# QRS959041_JiaLichuang.net
KiCad netlist of a schematic drawn in EasyEDA Pro
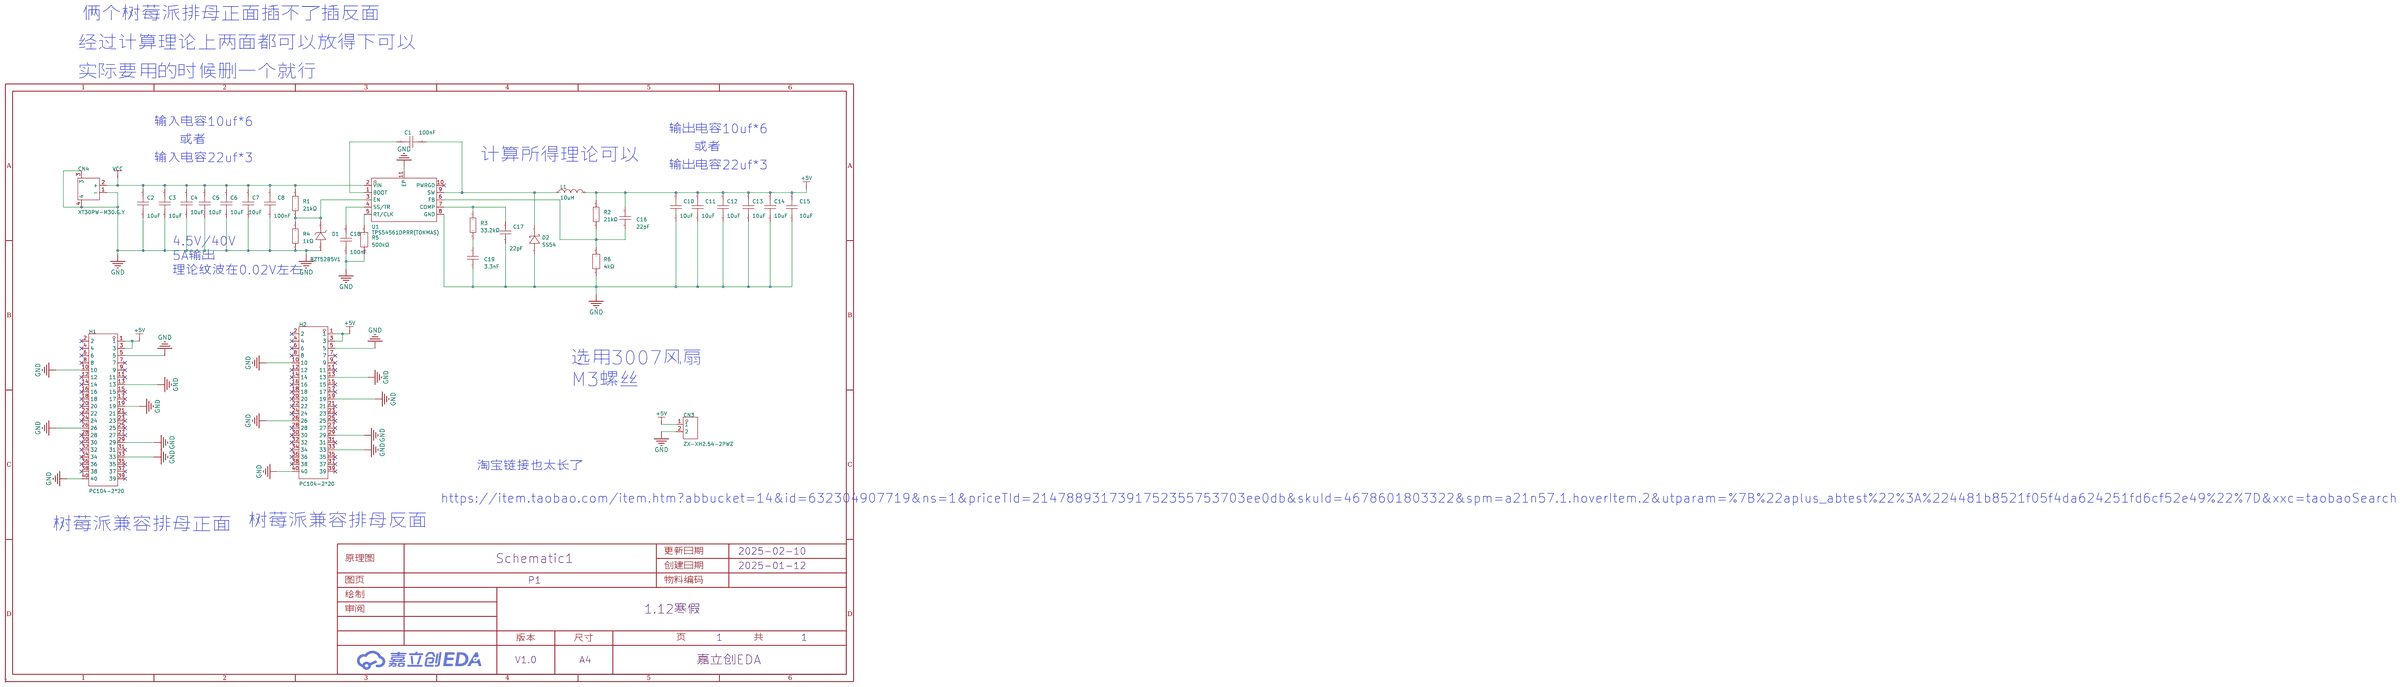
[diagram p0: schematic sheet]

(export (version "E")
  (design (tool "Eeschema 10.0.6"))
  (components
    (comp (ref "C1")
      (value "100nF")
      (footprint "easyedapro:C0603")
      (description "容值:100nF;精度:±10%;额定电压:50V;材质(温度系数):X7R;")
      (fields
        (field (name "Manufacturer Part") "CGA0603X7R104K500JT")
        (field (name "Manufacturer") "HRE(芯声)")
      )
      (libsource (lib "easyedapro") (part "CGA0603X7R104K500JT"))
    )
    (comp (ref "C2")
      (value "10uF")
      (footprint "easyedapro:C0805")
      (description "容值:10uF;精度:±10%;额定电压:50V;材质(温度系数):X5R;")
      (fields
        (field (name "Manufacturer Part") "GRM21BR61H106KE43L")
        (field (name "Manufacturer") "muRata(村田)")
      )
      (libsource (lib "easyedapro") (part "GRM21BR61H106KE43L"))
    )
    (comp (ref "C3")
      (value "10uF")
      (footprint "easyedapro:C0805")
      (description "容值:10uF;精度:±10%;额定电压:50V;材质(温度系数):X5R;")
      (fields
        (field (name "Manufacturer Part") "GRM21BR61H106KE43L")
        (field (name "Manufacturer") "muRata(村田)")
      )
      (libsource (lib "easyedapro") (part "GRM21BR61H106KE43L"))
    )
    (comp (ref "C4")
      (value "10uF")
      (footprint "easyedapro:C0805")
      (description "容值:10uF;精度:±10%;额定电压:50V;材质(温度系数):X5R;")
      (fields
        (field (name "Manufacturer Part") "GRM21BR61H106KE43L")
        (field (name "Manufacturer") "muRata(村田)")
      )
      (libsource (lib "easyedapro") (part "GRM21BR61H106KE43L"))
    )
    (comp (ref "C5")
      (value "10uF")
      (footprint "easyedapro:C0805")
      (description "容值:10uF;精度:±10%;额定电压:50V;材质(温度系数):X5R;")
      (fields
        (field (name "Manufacturer Part") "GRM21BR61H106KE43L")
        (field (name "Manufacturer") "muRata(村田)")
      )
      (libsource (lib "easyedapro") (part "GRM21BR61H106KE43L"))
    )
    (comp (ref "C6")
      (value "10uF")
      (footprint "easyedapro:C0805")
      (description "容值:10uF;精度:±10%;额定电压:50V;材质(温度系数):X5R;")
      (fields
        (field (name "Manufacturer Part") "GRM21BR61H106KE43L")
        (field (name "Manufacturer") "muRata(村田)")
      )
      (libsource (lib "easyedapro") (part "GRM21BR61H106KE43L"))
    )
    (comp (ref "C7")
      (value "10uF")
      (footprint "easyedapro:C0805")
      (description "容值:10uF;精度:±10%;额定电压:50V;材质(温度系数):X5R;")
      (fields
        (field (name "Manufacturer Part") "GRM21BR61H106KE43L")
        (field (name "Manufacturer") "muRata(村田)")
      )
      (libsource (lib "easyedapro") (part "GRM21BR61H106KE43L"))
    )
    (comp (ref "C8")
      (value "100nF")
      (footprint "easyedapro:C0603")
      (description "容值:100nF;精度:±10%;额定电压:50V;材质(温度系数):X7R;")
      (fields
        (field (name "Manufacturer Part") "CGA0603X7R104K500JT")
        (field (name "Manufacturer") "HRE(芯声)")
      )
      (libsource (lib "easyedapro") (part "CGA0603X7R104K500JT"))
    )
    (comp (ref "C10")
      (value "10uF")
      (footprint "easyedapro:C0805")
      (description "容值:10uF;精度:±10%;额定电压:50V;材质(温度系数):X5R;")
      (fields
        (field (name "Manufacturer Part") "GRM21BR61H106KE43L")
        (field (name "Manufacturer") "muRata(村田)")
      )
      (libsource (lib "easyedapro") (part "GRM21BR61H106KE43L"))
    )
    (comp (ref "C11")
      (value "10uF")
      (footprint "easyedapro:C0805")
      (description "容值:10uF;精度:±10%;额定电压:50V;材质(温度系数):X5R;")
      (fields
        (field (name "Manufacturer Part") "GRM21BR61H106KE43L")
        (field (name "Manufacturer") "muRata(村田)")
      )
      (libsource (lib "easyedapro") (part "GRM21BR61H106KE43L"))
    )
    (comp (ref "C12")
      (value "10uF")
      (footprint "easyedapro:C0805")
      (description "容值:10uF;精度:±10%;额定电压:50V;材质(温度系数):X5R;")
      (fields
        (field (name "Manufacturer Part") "GRM21BR61H106KE43L")
        (field (name "Manufacturer") "muRata(村田)")
      )
      (libsource (lib "easyedapro") (part "GRM21BR61H106KE43L"))
    )
    (comp (ref "C13")
      (value "10uF")
      (footprint "easyedapro:C0805")
      (description "容值:10uF;精度:±10%;额定电压:50V;材质(温度系数):X5R;")
      (fields
        (field (name "Manufacturer Part") "GRM21BR61H106KE43L")
        (field (name "Manufacturer") "muRata(村田)")
      )
      (libsource (lib "easyedapro") (part "GRM21BR61H106KE43L"))
    )
    (comp (ref "C14")
      (value "10uF")
      (footprint "easyedapro:C0805")
      (description "容值:10uF;精度:±10%;额定电压:50V;材质(温度系数):X5R;")
      (fields
        (field (name "Manufacturer Part") "GRM21BR61H106KE43L")
        (field (name "Manufacturer") "muRata(村田)")
      )
      (libsource (lib "easyedapro") (part "GRM21BR61H106KE43L"))
    )
    (comp (ref "C15")
      (value "10uF")
      (footprint "easyedapro:C0805")
      (description "容值:10uF;精度:±10%;额定电压:50V;材质(温度系数):X5R;")
      (fields
        (field (name "Manufacturer Part") "GRM21BR61H106KE43L")
        (field (name "Manufacturer") "muRata(村田)")
      )
      (libsource (lib "easyedapro") (part "GRM21BR61H106KE43L"))
    )
    (comp (ref "C16")
      (value "22pF")
      (footprint "easyedapro:C0603")
      (description "容值:22pF;精度:±5%;额定电压:50V;材质(温度系数):NP0;")
      (fields
        (field (name "Manufacturer Part") "CC0603JRNPO9BN220")
        (field (name "Manufacturer") "YAGEO(国巨)")
      )
      (libsource (lib "easyedapro") (part "CC0603JRNPO9BN220"))
    )
    (comp (ref "C17")
      (value "22pF")
      (footprint "easyedapro:C0603")
      (description "容值:22pF;精度:±5%;额定电压:50V;材质(温度系数):NP0;")
      (fields
        (field (name "Manufacturer Part") "CC0603JRNPO9BN220")
        (field (name "Manufacturer") "YAGEO(国巨)")
      )
      (libsource (lib "easyedapro") (part "CC0603JRNPO9BN220"))
    )
    (comp (ref "C18")
      (value "100nF")
      (footprint "easyedapro:C0603")
      (description "容值:100nF;精度:±10%;额定电压:50V;材质(温度系数):X7R;")
      (fields
        (field (name "Manufacturer Part") "CGA0603X7R104K500JT")
        (field (name "Manufacturer") "HRE(芯声)")
      )
      (libsource (lib "easyedapro") (part "CGA0603X7R104K500JT"))
    )
    (comp (ref "C19")
      (value "3.3nF")
      (footprint "easyedapro:C0603")
      (description "容值:3.3nF;精度:±10%;额定电压:50V;材质(温度系数):X7R;")
      (fields
        (field (name "Manufacturer Part") "CL10B332KB8NNNC")
        (field (name "Manufacturer") "SAMSUNG(三星)")
      )
      (libsource (lib "easyedapro") (part "CL10B332KB8NNNC"))
    )
    (comp (ref "CN3")
      (value "ZX-XH2.54-2PWZ")
      (footprint "easyedapro:CONN-TH_2P-P2.50_ZX-XH2.54-2PWZ")
      (fields (field (name "Manufacturer") "Megastar(兆星)"))
      (libsource (lib "easyedapro") (part "ZX-XH2.54-2PWZ"))
    )
    (comp (ref "CN4")
      (value "XT30PW-M30.G.Y")
      (footprint "easyedapro:CONN-TH_XT30PW-M")
      (description "类别:-;类型1:-;")
      (fields (field (name "Manufacturer") "AMASS(艾迈斯)"))
      (libsource (lib "easyedapro") (part "XT30PW-M"))
    )
    (comp (ref "D1")
      (value "BZT52B5V1")
      (footprint "easyedapro:SOD-123_L2.7-W1.6-LS3.7-RD")
      (description "二极管配置:独立式;稳压值(标称值):5.1V;稳压值(范围):5V~5.2V;功率(Pd):500mW;")
      (fields (field (name "Manufacturer") "宏迦橙"))
      (libsource (lib "easyedapro") (part "BZT52B5V1_C19077393"))
    )
    (comp (ref "D2")
      (value "SS54")
      (footprint "easyedapro:SMA_L4.3-W2.6-LS5.0-FD")
      (description "二极管配置:独立式;正向压降(Vf):550mV@5.0A;直流反向耐压(Vr):40V;整流电流:5A;")
      (fields (field (name "Manufacturer") "宏迦橙"))
      (libsource (lib "easyedapro") (part "SS54_C7420369"))
    )
    (comp (ref "H1")
      (value "PC104-2*20")
      (footprint "easyedapro:HDR-TH_40P-P2.54-V-F-R2-C20-S2.54-2")
      (fields (field (name "Manufacturer") "ZHOURI(洲日)"))
      (libsource (lib "easyedapro") (part "PC104-2*20"))
    )
    (comp (ref "H2")
      (value "PC104-2*20")
      (footprint "easyedapro:HDR-TH_40P-P2.54-V-F-R2-C20-S2.54-2")
      (fields (field (name "Manufacturer") "ZHOURI(洲日)"))
      (libsource (lib "easyedapro") (part "PC104-2*20"))
    )
    (comp (ref "L1")
      (value "10uH")
      (footprint "easyedapro:IND-SMD_L7.3-W6.8")
      (description "电感值:10uH;精度:±20%;额定电流:4.5A;饱和电流(Isat):5.5A;类型:一体成型电感;")
      (fields (field (name "Manufacturer Part") "FXL0630-100-M") (field (name "Manufacturer") "cjiang(长江微电)"))
      (libsource (lib "easyedapro") (part "FXL0630-100-M"))
    )
    (comp (ref "R1")
      (value "21kΩ")
      (footprint "easyedapro:R0603")
      (description "电阻类型:厚膜电阻;阻值:21kΩ;精度:±1%;功率:100mW;最大工作电压:75V;温度系数:±100ppm/°C;")
      (fields
        (field (name "Manufacturer Part") "0603WAF2102T5E")
        (field (name "Manufacturer") "UNI-ROYAL(厚声)")
      )
      (libsource (lib "easyedapro") (part "0603WAF2102T5E"))
    )
    (comp (ref "R2")
      (value "21kΩ")
      (footprint "easyedapro:R0603")
      (description "电阻类型:厚膜电阻;阻值:21kΩ;精度:±1%;功率:100mW;最大工作电压:75V;温度系数:±100ppm/°C;")
      (fields
        (field (name "Manufacturer Part") "0603WAF2102T5E")
        (field (name "Manufacturer") "UNI-ROYAL(厚声)")
      )
      (libsource (lib "easyedapro") (part "0603WAF2102T5E"))
    )
    (comp (ref "R3")
      (value "33.2kΩ")
      (footprint "easyedapro:R0603")
      (description "电阻类型:厚膜电阻;阻值:33.2kΩ;精度:±1%;功率:100mW;最大工作电压:75V;温度系数:±100ppm/°C;")
      (fields (field (name "Manufacturer Part") "RC0603FR-0733K2L") (field (name "Manufacturer") "YAGEO(国巨)"))
      (libsource (lib "easyedapro") (part "RC0603FR-0733K2L"))
    )
    (comp (ref "R4")
      (value "1kΩ")
      (footprint "easyedapro:R0603")
      (description "电阻类型:厚膜电阻;阻值:1kΩ;精度:±1%;功率:100mW;最大工作电压:75V;温度系数:±100ppm/°C;")
      (fields
        (field (name "Manufacturer Part") "0603WAF1001T5E")
        (field (name "Manufacturer") "UNI-ROYAL(厚声)")
      )
      (libsource (lib "easyedapro") (part "0603WAF1001T5E"))
    )
    (comp (ref "R5")
      (value "500kΩ")
      (footprint "easyedapro:R0603")
      (description "电阻类型:薄膜电阻;阻值:500kΩ;精度:±0.1%;功率:100mW;最大工作电压:50V;温度系数:±25ppm/°C;")
      (fields (field (name "Manufacturer Part") "AR03BTCX5003N") (field (name "Manufacturer") "Viking(光颉)"))
      (libsource (lib "easyedapro") (part "AR03BTCX5003N"))
    )
    (comp (ref "R6")
      (value "4kΩ")
      (footprint "easyedapro:R0603")
      (description "电阻类型:薄膜电阻;阻值:4kΩ;精度:±1%;")
      (fields (field (name "Manufacturer Part") "ARG03FTC4001N") (field (name "Manufacturer") "Viking(光颉)"))
      (libsource (lib "easyedapro") (part "ARG03FTC4001N"))
    )
    (comp (ref "U1")
      (value "TPS54561DPRR(TOKMAS)")
      (footprint "easyedapro:WDFN-10_L4.0-W4.0-P0.80-BL-EP")
      (description "功能类型:降压型;输出类型:可调;输入电压:4.5V~60V;输出电压:800mV~59V;输出电流(最大值):5A;")
      (fields (field (name "Manufacturer") "Tokmas(托克马斯)"))
      (libsource (lib "easyedapro") (part "TPS54561DPRR(TOKMAS)"))
    )
  )
  (nets
    (net (code "1") (name "+5V") (class "Default")
      (node (ref "C10") (pin "2") (pinfunction "2_2") (pintype "unspecified"))
      (node (ref "C11") (pin "2") (pinfunction "2_2") (pintype "unspecified"))
      (node (ref "C12") (pin "2") (pinfunction "2_2") (pintype "unspecified"))
      (node (ref "C13") (pin "2") (pinfunction "2_2") (pintype "unspecified"))
      (node (ref "C14") (pin "2") (pinfunction "2_2") (pintype "unspecified"))
      (node (ref "C15") (pin "2") (pinfunction "2_2") (pintype "unspecified"))
      (node (ref "C16") (pin "1") (pinfunction "1_1") (pintype "input"))
      (node (ref "CN3") (pin "1") (pinfunction "1_1") (pintype "unspecified"))
      (node (ref "H1") (pin "1") (pinfunction "1_1") (pintype "unspecified"))
      (node (ref "H1") (pin "3") (pinfunction "3_3") (pintype "unspecified"))
      (node (ref "H2") (pin "1") (pinfunction "1_1") (pintype "unspecified"))
      (node (ref "H2") (pin "3") (pinfunction "3_3") (pintype "unspecified"))
      (node (ref "L1") (pin "2") (pinfunction "2_2") (pintype "unspecified"))
      (node (ref "R2") (pin "2") (pinfunction "2_2") (pintype "input"))
    )
    (net (code "2") (name "GND") (class "Default")
      (node (ref "C10") (pin "1") (pinfunction "1_1") (pintype "unspecified"))
      (node (ref "C11") (pin "1") (pinfunction "1_1") (pintype "unspecified"))
      (node (ref "C12") (pin "1") (pinfunction "1_1") (pintype "unspecified"))
      (node (ref "C13") (pin "1") (pinfunction "1_1") (pintype "unspecified"))
      (node (ref "C14") (pin "1") (pinfunction "1_1") (pintype "unspecified"))
      (node (ref "C15") (pin "1") (pinfunction "1_1") (pintype "unspecified"))
      (node (ref "C17") (pin "2") (pinfunction "2_2") (pintype "input"))
      (node (ref "C18") (pin "1") (pinfunction "1_1") (pintype "unspecified"))
      (node (ref "C19") (pin "1") (pinfunction "1_1") (pintype "input"))
      (node (ref "C2") (pin "1") (pinfunction "1_1") (pintype "unspecified"))
      (node (ref "C3") (pin "1") (pinfunction "1_1") (pintype "unspecified"))
      (node (ref "C4") (pin "1") (pinfunction "1_1") (pintype "unspecified"))
      (node (ref "C5") (pin "1") (pinfunction "1_1") (pintype "unspecified"))
      (node (ref "C6") (pin "1") (pinfunction "1_1") (pintype "unspecified"))
      (node (ref "C7") (pin "1") (pinfunction "1_1") (pintype "unspecified"))
      (node (ref "C8") (pin "1") (pinfunction "1_1") (pintype "unspecified"))
      (node (ref "CN3") (pin "2") (pinfunction "2_2") (pintype "unspecified"))
      (node (ref "CN4") (pin "1") (pinfunction "-_1") (pintype "unspecified"))
      (node (ref "CN4") (pin "3") (pinfunction "3_3") (pintype "unspecified"))
      (node (ref "CN4") (pin "4") (pinfunction "4_4") (pintype "unspecified"))
      (node (ref "D1") (pin "2") (pinfunction "A_2") (pintype "unspecified"))
      (node (ref "D2") (pin "1") (pinfunction "A_1") (pintype "unspecified"))
      (node (ref "H1") (pin "10") (pinfunction "10_10") (pintype "unspecified"))
      (node (ref "H1") (pin "13") (pinfunction "13_13") (pintype "unspecified"))
      (node (ref "H1") (pin "19") (pinfunction "19_19") (pintype "unspecified"))
      (node (ref "H1") (pin "26") (pinfunction "26_26") (pintype "unspecified"))
      (node (ref "H1") (pin "29") (pinfunction "29_29") (pintype "unspecified"))
      (node (ref "H1") (pin "33") (pinfunction "33_33") (pintype "unspecified"))
      (node (ref "H1") (pin "40") (pinfunction "40_40") (pintype "unspecified"))
      (node (ref "H1") (pin "5") (pinfunction "5_5") (pintype "unspecified"))
      (node (ref "H2") (pin "10") (pinfunction "10_10") (pintype "unspecified"))
      (node (ref "H2") (pin "13") (pinfunction "13_13") (pintype "unspecified"))
      (node (ref "H2") (pin "19") (pinfunction "19_19") (pintype "unspecified"))
      (node (ref "H2") (pin "26") (pinfunction "26_26") (pintype "unspecified"))
      (node (ref "H2") (pin "29") (pinfunction "29_29") (pintype "unspecified"))
      (node (ref "H2") (pin "33") (pinfunction "33_33") (pintype "unspecified"))
      (node (ref "H2") (pin "40") (pinfunction "40_40") (pintype "unspecified"))
      (node (ref "H2") (pin "5") (pinfunction "5_5") (pintype "unspecified"))
      (node (ref "R4") (pin "1") (pinfunction "1_1") (pintype "input"))
      (node (ref "R5") (pin "1") (pinfunction "1_1") (pintype "unspecified"))
      (node (ref "R6") (pin "1") (pinfunction "1_1") (pintype "unspecified"))
      (node (ref "U1") (pin "11") (pinfunction "EP_11") (pintype "unspecified"))
      (node (ref "U1") (pin "8") (pinfunction "GND_8") (pintype "unspecified"))
    )
    (net (code "3") (name "Net-(C19-Pad2)") (class "Default")
      (node (ref "C19") (pin "2") (pinfunction "2_2") (pintype "input"))
      (node (ref "R3") (pin "1") (pinfunction "1_1") (pintype "unspecified"))
    )
    (net (code "4") (name "Net-(D1-K)") (class "Default")
      (node (ref "D1") (pin "1") (pinfunction "K_1") (pintype "unspecified"))
      (node (ref "R1") (pin "1") (pinfunction "1_1") (pintype "input"))
      (node (ref "R4") (pin "2") (pinfunction "2_2") (pintype "input"))
      (node (ref "U1") (pin "3") (pinfunction "EN_3") (pintype "unspecified"))
    )
    (net (code "5") (name "Net-(D2-K)") (class "Default")
      (node (ref "C1") (pin "2") (pinfunction "2_2") (pintype "unspecified"))
      (node (ref "D2") (pin "2") (pinfunction "K_2") (pintype "unspecified"))
      (node (ref "L1") (pin "1") (pinfunction "1_1") (pintype "unspecified"))
      (node (ref "U1") (pin "9") (pinfunction "SW_9") (pintype "unspecified"))
    )
    (net (code "6") (name "Net-(U1-BOOT)") (class "Default")
      (node (ref "C1") (pin "1") (pinfunction "1_1") (pintype "unspecified"))
      (node (ref "U1") (pin "1") (pinfunction "BOOT_1") (pintype "unspecified"))
    )
    (net (code "7") (name "Net-(U1-COMP)") (class "Default")
      (node (ref "C17") (pin "1") (pinfunction "1_1") (pintype "input"))
      (node (ref "R3") (pin "2") (pinfunction "2_2") (pintype "unspecified"))
      (node (ref "U1") (pin "7") (pinfunction "COMP_7") (pintype "unspecified"))
    )
    (net (code "8") (name "Net-(U1-FB)") (class "Default")
      (node (ref "C16") (pin "2") (pinfunction "2_2") (pintype "input"))
      (node (ref "R2") (pin "1") (pinfunction "1_1") (pintype "input"))
      (node (ref "R6") (pin "2") (pinfunction "2_2") (pintype "unspecified"))
      (node (ref "U1") (pin "6") (pinfunction "FB_6") (pintype "unspecified"))
    )
    (net (code "9") (name "Net-(U1-RT{slash}CLK)") (class "Default")
      (node (ref "R5") (pin "2") (pinfunction "2_2") (pintype "unspecified"))
      (node (ref "U1") (pin "5") (pinfunction "RT/CLK_5") (pintype "unspecified"))
    )
    (net (code "10") (name "Net-(U1-SS{slash}TR)") (class "Default")
      (node (ref "C18") (pin "2") (pinfunction "2_2") (pintype "unspecified"))
      (node (ref "U1") (pin "4") (pinfunction "SS/TR_4") (pintype "unspecified"))
    )
    (net (code "11") (name "VCC") (class "Default")
      (node (ref "C2") (pin "2") (pinfunction "2_2") (pintype "unspecified"))
      (node (ref "C3") (pin "2") (pinfunction "2_2") (pintype "unspecified"))
      (node (ref "C4") (pin "2") (pinfunction "2_2") (pintype "unspecified"))
      (node (ref "C5") (pin "2") (pinfunction "2_2") (pintype "unspecified"))
      (node (ref "C6") (pin "2") (pinfunction "2_2") (pintype "unspecified"))
      (node (ref "C7") (pin "2") (pinfunction "2_2") (pintype "unspecified"))
      (node (ref "C8") (pin "2") (pinfunction "2_2") (pintype "unspecified"))
      (node (ref "CN4") (pin "2") (pinfunction "+_2") (pintype "unspecified"))
      (node (ref "R1") (pin "2") (pinfunction "2_2") (pintype "input"))
      (node (ref "U1") (pin "2") (pinfunction "VIN_2") (pintype "unspecified"))
    )
    (net (code "12") (name "unconnected-(H1-Pad2)") (class "Default")
      (node (ref "H1") (pin "2") (pinfunction "2_2") (pintype "unspecified+no_connect"))
    )
    (net (code "13") (name "unconnected-(H1-Pad4)") (class "Default")
      (node (ref "H1") (pin "4") (pinfunction "4_4") (pintype "unspecified+no_connect"))
    )
    (net (code "14") (name "unconnected-(H1-Pad6)") (class "Default")
      (node (ref "H1") (pin "6") (pinfunction "6_6") (pintype "unspecified+no_connect"))
    )
    (net (code "15") (name "unconnected-(H1-Pad7)") (class "Default")
      (node (ref "H1") (pin "7") (pinfunction "7_7") (pintype "unspecified+no_connect"))
    )
    (net (code "16") (name "unconnected-(H1-Pad8)") (class "Default")
      (node (ref "H1") (pin "8") (pinfunction "8_8") (pintype "unspecified+no_connect"))
    )
    (net (code "17") (name "unconnected-(H1-Pad9)") (class "Default")
      (node (ref "H1") (pin "9") (pinfunction "9_9") (pintype "unspecified+no_connect"))
    )
    (net (code "18") (name "unconnected-(H1-Pad11)") (class "Default")
      (node (ref "H1") (pin "11") (pinfunction "11_11") (pintype "unspecified+no_connect"))
    )
    (net (code "19") (name "unconnected-(H1-Pad12)") (class "Default")
      (node (ref "H1") (pin "12") (pinfunction "12_12") (pintype "unspecified+no_connect"))
    )
    (net (code "20") (name "unconnected-(H1-Pad14)") (class "Default")
      (node (ref "H1") (pin "14") (pinfunction "14_14") (pintype "unspecified+no_connect"))
    )
    (net (code "21") (name "unconnected-(H1-Pad15)") (class "Default")
      (node (ref "H1") (pin "15") (pinfunction "15_15") (pintype "unspecified+no_connect"))
    )
    (net (code "22") (name "unconnected-(H1-Pad16)") (class "Default")
      (node (ref "H1") (pin "16") (pinfunction "16_16") (pintype "unspecified+no_connect"))
    )
    (net (code "23") (name "unconnected-(H1-Pad17)") (class "Default")
      (node (ref "H1") (pin "17") (pinfunction "17_17") (pintype "unspecified+no_connect"))
    )
    (net (code "24") (name "unconnected-(H1-Pad18)") (class "Default")
      (node (ref "H1") (pin "18") (pinfunction "18_18") (pintype "unspecified+no_connect"))
    )
    (net (code "25") (name "unconnected-(H1-Pad20)") (class "Default")
      (node (ref "H1") (pin "20") (pinfunction "20_20") (pintype "unspecified+no_connect"))
    )
    (net (code "26") (name "unconnected-(H1-Pad21)") (class "Default")
      (node (ref "H1") (pin "21") (pinfunction "21_21") (pintype "unspecified+no_connect"))
    )
    (net (code "27") (name "unconnected-(H1-Pad22)") (class "Default")
      (node (ref "H1") (pin "22") (pinfunction "22_22") (pintype "unspecified+no_connect"))
    )
    (net (code "28") (name "unconnected-(H1-Pad23)") (class "Default")
      (node (ref "H1") (pin "23") (pinfunction "23_23") (pintype "unspecified+no_connect"))
    )
    (net (code "29") (name "unconnected-(H1-Pad24)") (class "Default")
      (node (ref "H1") (pin "24") (pinfunction "24_24") (pintype "unspecified+no_connect"))
    )
    (net (code "30") (name "unconnected-(H1-Pad25)") (class "Default")
      (node (ref "H1") (pin "25") (pinfunction "25_25") (pintype "unspecified+no_connect"))
    )
    (net (code "31") (name "unconnected-(H1-Pad27)") (class "Default")
      (node (ref "H1") (pin "27") (pinfunction "27_27") (pintype "unspecified+no_connect"))
    )
    (net (code "32") (name "unconnected-(H1-Pad28)") (class "Default")
      (node (ref "H1") (pin "28") (pinfunction "28_28") (pintype "unspecified+no_connect"))
    )
    (net (code "33") (name "unconnected-(H1-Pad30)") (class "Default")
      (node (ref "H1") (pin "30") (pinfunction "30_30") (pintype "unspecified+no_connect"))
    )
    (net (code "34") (name "unconnected-(H1-Pad31)") (class "Default")
      (node (ref "H1") (pin "31") (pinfunction "31_31") (pintype "unspecified+no_connect"))
    )
    (net (code "35") (name "unconnected-(H1-Pad32)") (class "Default")
      (node (ref "H1") (pin "32") (pinfunction "32_32") (pintype "unspecified+no_connect"))
    )
    (net (code "36") (name "unconnected-(H1-Pad34)") (class "Default")
      (node (ref "H1") (pin "34") (pinfunction "34_34") (pintype "unspecified+no_connect"))
    )
    (net (code "37") (name "unconnected-(H1-Pad35)") (class "Default")
      (node (ref "H1") (pin "35") (pinfunction "35_35") (pintype "unspecified+no_connect"))
    )
    (net (code "38") (name "unconnected-(H1-Pad36)") (class "Default")
      (node (ref "H1") (pin "36") (pinfunction "36_36") (pintype "unspecified+no_connect"))
    )
    (net (code "39") (name "unconnected-(H1-Pad37)") (class "Default")
      (node (ref "H1") (pin "37") (pinfunction "37_37") (pintype "unspecified+no_connect"))
    )
    (net (code "40") (name "unconnected-(H1-Pad38)") (class "Default")
      (node (ref "H1") (pin "38") (pinfunction "38_38") (pintype "unspecified+no_connect"))
    )
    (net (code "41") (name "unconnected-(H1-Pad39)") (class "Default")
      (node (ref "H1") (pin "39") (pinfunction "39_39") (pintype "unspecified+no_connect"))
    )
    (net (code "42") (name "unconnected-(H2-Pad2)") (class "Default")
      (node (ref "H2") (pin "2") (pinfunction "2_2") (pintype "unspecified+no_connect"))
    )
    (net (code "43") (name "unconnected-(H2-Pad4)") (class "Default")
      (node (ref "H2") (pin "4") (pinfunction "4_4") (pintype "unspecified+no_connect"))
    )
    (net (code "44") (name "unconnected-(H2-Pad6)") (class "Default")
      (node (ref "H2") (pin "6") (pinfunction "6_6") (pintype "unspecified+no_connect"))
    )
    (net (code "45") (name "unconnected-(H2-Pad7)") (class "Default")
      (node (ref "H2") (pin "7") (pinfunction "7_7") (pintype "unspecified+no_connect"))
    )
    (net (code "46") (name "unconnected-(H2-Pad8)") (class "Default")
      (node (ref "H2") (pin "8") (pinfunction "8_8") (pintype "unspecified+no_connect"))
    )
    (net (code "47") (name "unconnected-(H2-Pad9)") (class "Default")
      (node (ref "H2") (pin "9") (pinfunction "9_9") (pintype "unspecified+no_connect"))
    )
    (net (code "48") (name "unconnected-(H2-Pad11)") (class "Default")
      (node (ref "H2") (pin "11") (pinfunction "11_11") (pintype "unspecified+no_connect"))
    )
    (net (code "49") (name "unconnected-(H2-Pad12)") (class "Default")
      (node (ref "H2") (pin "12") (pinfunction "12_12") (pintype "unspecified+no_connect"))
    )
    (net (code "50") (name "unconnected-(H2-Pad14)") (class "Default")
      (node (ref "H2") (pin "14") (pinfunction "14_14") (pintype "unspecified+no_connect"))
    )
    (net (code "51") (name "unconnected-(H2-Pad15)") (class "Default")
      (node (ref "H2") (pin "15") (pinfunction "15_15") (pintype "unspecified+no_connect"))
    )
    (net (code "52") (name "unconnected-(H2-Pad16)") (class "Default")
      (node (ref "H2") (pin "16") (pinfunction "16_16") (pintype "unspecified+no_connect"))
    )
    (net (code "53") (name "unconnected-(H2-Pad17)") (class "Default")
      (node (ref "H2") (pin "17") (pinfunction "17_17") (pintype "unspecified+no_connect"))
    )
    (net (code "54") (name "unconnected-(H2-Pad18)") (class "Default")
      (node (ref "H2") (pin "18") (pinfunction "18_18") (pintype "unspecified+no_connect"))
    )
    (net (code "55") (name "unconnected-(H2-Pad20)") (class "Default")
      (node (ref "H2") (pin "20") (pinfunction "20_20") (pintype "unspecified+no_connect"))
    )
    (net (code "56") (name "unconnected-(H2-Pad21)") (class "Default")
      (node (ref "H2") (pin "21") (pinfunction "21_21") (pintype "unspecified+no_connect"))
    )
    (net (code "57") (name "unconnected-(H2-Pad22)") (class "Default")
      (node (ref "H2") (pin "22") (pinfunction "22_22") (pintype "unspecified+no_connect"))
    )
    (net (code "58") (name "unconnected-(H2-Pad23)") (class "Default")
      (node (ref "H2") (pin "23") (pinfunction "23_23") (pintype "unspecified+no_connect"))
    )
    (net (code "59") (name "unconnected-(H2-Pad24)") (class "Default")
      (node (ref "H2") (pin "24") (pinfunction "24_24") (pintype "unspecified+no_connect"))
    )
    (net (code "60") (name "unconnected-(H2-Pad25)") (class "Default")
      (node (ref "H2") (pin "25") (pinfunction "25_25") (pintype "unspecified+no_connect"))
    )
    (net (code "61") (name "unconnected-(H2-Pad27)") (class "Default")
      (node (ref "H2") (pin "27") (pinfunction "27_27") (pintype "unspecified+no_connect"))
    )
    (net (code "62") (name "unconnected-(H2-Pad28)") (class "Default")
      (node (ref "H2") (pin "28") (pinfunction "28_28") (pintype "unspecified+no_connect"))
    )
    (net (code "63") (name "unconnected-(H2-Pad30)") (class "Default")
      (node (ref "H2") (pin "30") (pinfunction "30_30") (pintype "unspecified+no_connect"))
    )
    (net (code "64") (name "unconnected-(H2-Pad31)") (class "Default")
      (node (ref "H2") (pin "31") (pinfunction "31_31") (pintype "unspecified+no_connect"))
    )
    (net (code "65") (name "unconnected-(H2-Pad32)") (class "Default")
      (node (ref "H2") (pin "32") (pinfunction "32_32") (pintype "unspecified+no_connect"))
    )
    (net (code "66") (name "unconnected-(H2-Pad34)") (class "Default")
      (node (ref "H2") (pin "34") (pinfunction "34_34") (pintype "unspecified+no_connect"))
    )
    (net (code "67") (name "unconnected-(H2-Pad35)") (class "Default")
      (node (ref "H2") (pin "35") (pinfunction "35_35") (pintype "unspecified+no_connect"))
    )
    (net (code "68") (name "unconnected-(H2-Pad36)") (class "Default")
      (node (ref "H2") (pin "36") (pinfunction "36_36") (pintype "unspecified+no_connect"))
    )
    (net (code "69") (name "unconnected-(H2-Pad37)") (class "Default")
      (node (ref "H2") (pin "37") (pinfunction "37_37") (pintype "unspecified+no_connect"))
    )
    (net (code "70") (name "unconnected-(H2-Pad38)") (class "Default")
      (node (ref "H2") (pin "38") (pinfunction "38_38") (pintype "unspecified+no_connect"))
    )
    (net (code "71") (name "unconnected-(H2-Pad39)") (class "Default")
      (node (ref "H2") (pin "39") (pinfunction "39_39") (pintype "unspecified+no_connect"))
    )
    (net (code "72") (name "unconnected-(U1-PWRGD-Pad10)") (class "Default")
      (node (ref "U1") (pin "10") (pinfunction "PWRGD_10") (pintype "unspecified+no_connect"))
    )
  )
)
